# Item.net
KiCad netlist of a schematic drawn in Altium Designer
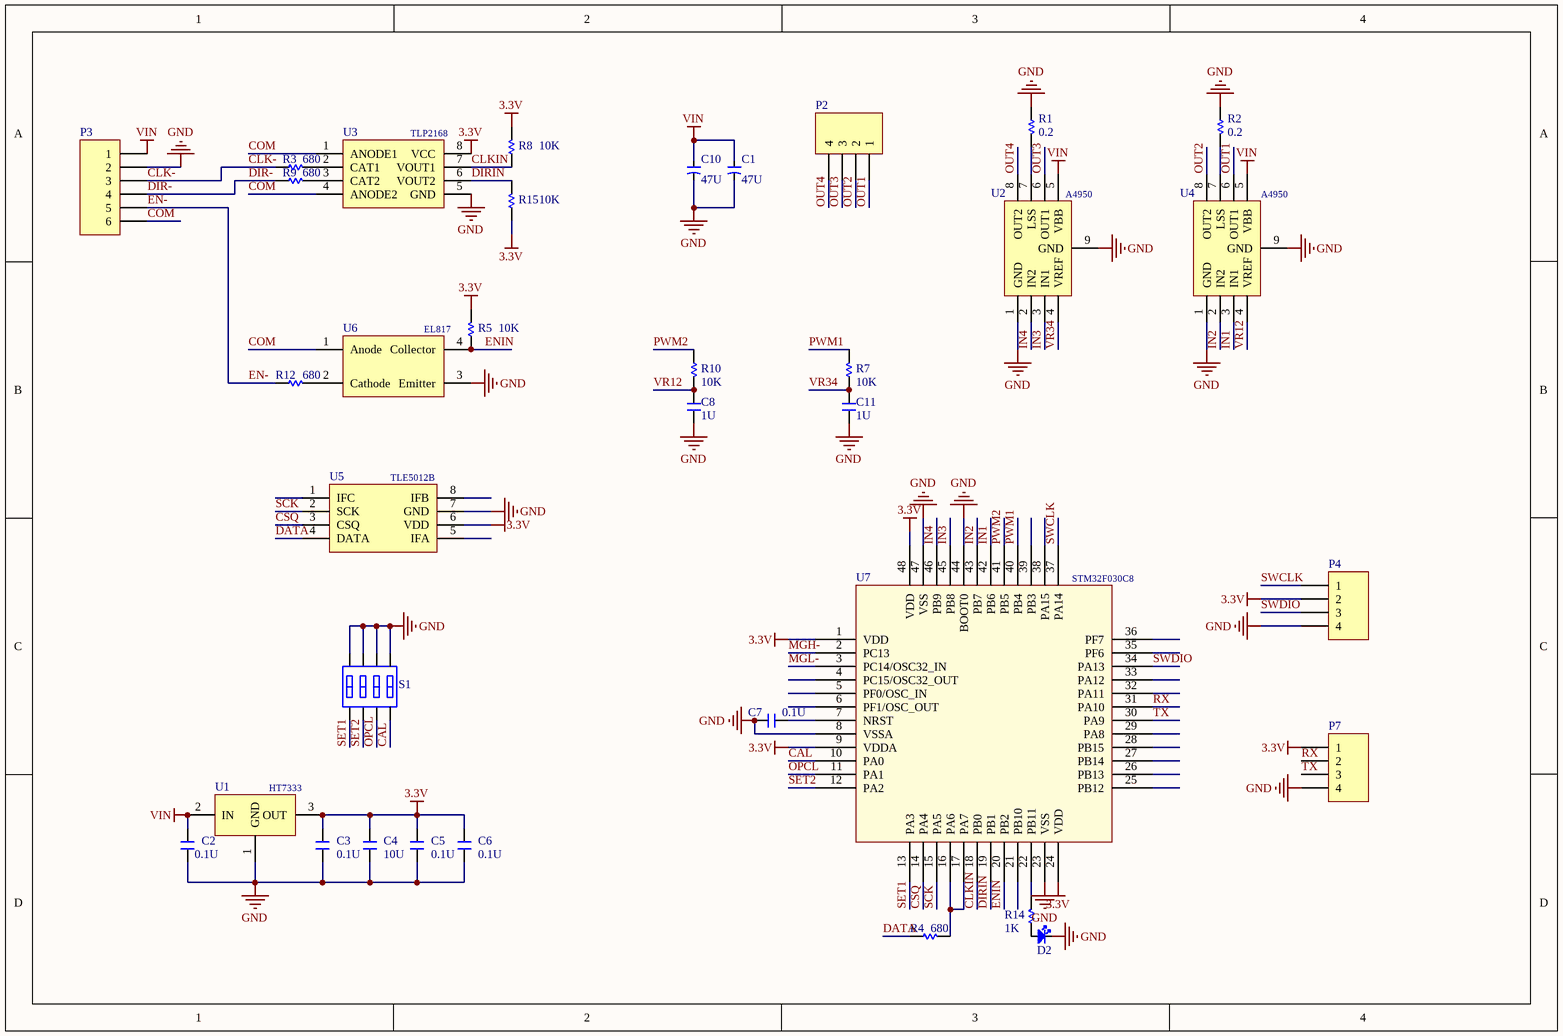
[diagram p0: Item.SchDoc]

(export (version "E")
  (design (tool "Eeschema 10.0.6"))
  (components
    (comp (ref "C1")
      (value "47U")
      (footprint "CAP6377")
      (description "Polarized Capacitor (Axial)")
      (fields (field (name "Comment") "CAP POL") (field (name "PUBLISHER") "Altium Limited"))
      (libsource (lib "MySchib") (part "CAP POL"))
    )
    (comp (ref "C2")
      (value "0.1U")
      (footprint "0805")
      (description "Capacitor")
      (fields (field (name "Comment") "CAP") (field (name "PUBLISHER") "Altium Limited"))
      (libsource (lib "MySchib") (part "CAP"))
    )
    (comp (ref "C3")
      (value "0.1U")
      (footprint "0805")
      (description "Capacitor")
      (fields (field (name "Comment") "CAP") (field (name "PUBLISHER") "Altium Limited"))
      (libsource (lib "MySchib") (part "CAP"))
    )
    (comp (ref "C4")
      (value "10U")
      (footprint "0805")
      (description "Capacitor")
      (fields (field (name "Comment") "CAP") (field (name "PUBLISHER") "Altium Limited"))
      (libsource (lib "MySchib") (part "CAP"))
    )
    (comp (ref "C5")
      (value "0.1U")
      (footprint "0805")
      (description "Capacitor")
      (fields (field (name "Comment") "CAP") (field (name "PUBLISHER") "Altium Limited"))
      (libsource (lib "MySchib") (part "CAP"))
    )
    (comp (ref "C6")
      (value "0.1U")
      (footprint "0805")
      (description "Capacitor")
      (fields (field (name "Comment") "CAP") (field (name "PUBLISHER") "Altium Limited"))
      (libsource (lib "MySchib") (part "CAP"))
    )
    (comp (ref "C7")
      (value "0.1U")
      (footprint "0805")
      (description "Capacitor")
      (fields (field (name "Comment") "CAP") (field (name "PUBLISHER") "Altium Limited"))
      (libsource (lib "MySchib") (part "CAP"))
    )
    (comp (ref "C8")
      (value "1U")
      (footprint "0805")
      (description "Capacitor")
      (fields (field (name "Comment") "CAP") (field (name "PUBLISHER") "Altium Limited"))
      (libsource (lib "MySchib") (part "CAP"))
    )
    (comp (ref "C10")
      (value "47U")
      (footprint "CAP6377")
      (description "Polarized Capacitor (Axial)")
      (fields (field (name "Comment") "CAP POL") (field (name "PUBLISHER") "Altium Limited"))
      (libsource (lib "MySchib") (part "CAP POL"))
    )
    (comp (ref "C11")
      (value "1U")
      (footprint "0805")
      (description "Capacitor")
      (fields (field (name "Comment") "CAP") (field (name "PUBLISHER") "Altium Limited"))
      (libsource (lib "MySchib") (part "CAP"))
    )
    (comp (ref "D2")
      (value "LED")
      (footprint "0805")
      (description "Typical INFRARED GaAs LED")
      (fields (field (name "PUBLISHER") "Altium Limited"))
      (libsource (lib "MySchib") (part "LED"))
    )
    (comp (ref "P2")
      (value "HEADER4")
      (footprint "XH-4")
      (description "Header, 4-Pin")
      (fields (field (name "PUBLISHER") "Altium Limited"))
      (libsource (lib "MySchib") (part "HEADER4"))
    )
    (comp (ref "P3")
      (value "HEADER6")
      (footprint "XH-6")
      (description "Header, 6-Pin")
      (fields (field (name "PUBLISHER") "Altium Limited"))
      (libsource (lib "MySchib") (part "HEADER6"))
    )
    (comp (ref "P4")
      (value "HEADER4")
      (footprint "4P-1.27MM")
      (description "Header, 4-Pin")
      (fields (field (name "PUBLISHER") "Altium Limited"))
      (libsource (lib "MySchib") (part "HEADER4"))
    )
    (comp (ref "P7")
      (value "HEADER4")
      (footprint "4P-1.27MM")
      (description "Header, 4-Pin")
      (fields (field (name "PUBLISHER") "Altium Limited"))
      (libsource (lib "MySchib") (part "HEADER4"))
    )
    (comp (ref "R1")
      (value "0.2")
      (footprint "1206")
      (description "Resistor")
      (fields (field (name "Comment") "RES") (field (name "PUBLISHER") "Altium Limited"))
      (libsource (lib "MySchib") (part "RES"))
    )
    (comp (ref "R2")
      (value "0.2")
      (footprint "1206")
      (description "Resistor")
      (fields (field (name "Comment") "RES") (field (name "PUBLISHER") "Altium Limited"))
      (libsource (lib "MySchib") (part "RES"))
    )
    (comp (ref "R3")
      (value "680")
      (footprint "0805")
      (description "Resistor")
      (fields (field (name "Comment") "RES") (field (name "PUBLISHER") "Altium Limited"))
      (libsource (lib "MySchib") (part "RES"))
    )
    (comp (ref "R4")
      (value "680")
      (footprint "0805")
      (description "Resistor")
      (fields (field (name "Comment") "RES") (field (name "PUBLISHER") "Altium Limited"))
      (libsource (lib "MySchib") (part "RES"))
    )
    (comp (ref "R5")
      (value "10K")
      (footprint "0805")
      (description "Resistor")
      (fields (field (name "Comment") "RES") (field (name "PUBLISHER") "Altium Limited"))
      (libsource (lib "MySchib") (part "RES"))
    )
    (comp (ref "R7")
      (value "10K")
      (footprint "0805")
      (description "Resistor")
      (fields (field (name "Comment") "RES") (field (name "PUBLISHER") "Altium Limited"))
      (libsource (lib "MySchib") (part "RES"))
    )
    (comp (ref "R8")
      (value "10K")
      (footprint "0805")
      (description "Resistor")
      (fields (field (name "Comment") "RES") (field (name "PUBLISHER") "Altium Limited"))
      (libsource (lib "MySchib") (part "RES"))
    )
    (comp (ref "R9")
      (value "680")
      (footprint "0805")
      (description "Resistor")
      (fields (field (name "Comment") "RES") (field (name "PUBLISHER") "Altium Limited"))
      (libsource (lib "MySchib") (part "RES"))
    )
    (comp (ref "R10")
      (value "10K")
      (footprint "0805")
      (description "Resistor")
      (fields (field (name "Comment") "RES") (field (name "PUBLISHER") "Altium Limited"))
      (libsource (lib "MySchib") (part "RES"))
    )
    (comp (ref "R12")
      (value "680")
      (footprint "0805")
      (description "Resistor")
      (fields (field (name "Comment") "RES") (field (name "PUBLISHER") "Altium Limited"))
      (libsource (lib "MySchib") (part "RES"))
    )
    (comp (ref "R14")
      (value "1K")
      (footprint "0805")
      (description "Resistor")
      (fields (field (name "Comment") "RES") (field (name "PUBLISHER") "Altium Limited"))
      (libsource (lib "MySchib") (part "RES"))
    )
    (comp (ref "R15")
      (value "10K")
      (footprint "0805")
      (description "Resistor")
      (fields (field (name "Comment") "RES") (field (name "PUBLISHER") "Altium Limited"))
      (libsource (lib "MySchib") (part "RES"))
    )
    (comp (ref "S1")
      (value "SWDIP-4")
      (footprint "SWDIP-4")
      (description "DIP Switch, 4Position, SPST")
      (fields (field (name "PUBLISHER") "Altium Limited"))
      (libsource (lib "MySchib") (part "SWDIP-4"))
    )
    (comp (ref "U1")
      (value "HT7333")
      (footprint "SOT89")
      (description "Positive Voltage Regulator")
      (fields (field (name "PUBLISHER") "Altium Limited"))
      (libsource (lib "MySchib") (part "HT7333"))
    )
    (comp (ref "U2")
      (value "A4950")
      (footprint "SOIC-8_A4950")
      (description "Dual Full-Bridge  DMOS PWM Motor Driver")
      (libsource (lib "MySchib") (part "A4950"))
    )
    (comp (ref "U3")
      (value "TLP2168")
      (footprint "SO-8_3.9mm")
      (description "HIGH SPEED 10MBit/s LOGIC GATE  PHOTOCOUPLER")
      (libsource (lib "MySchib") (part "TLP2168"))
    )
    (comp (ref "U4")
      (value "A4950")
      (footprint "SOIC-8_A4950")
      (description "Dual Full-Bridge  DMOS PWM Motor Driver")
      (libsource (lib "MySchib") (part "A4950"))
    )
    (comp (ref "U5")
      (value "TLE5012B")
      (footprint "PG-DSO-8F")
      (description "GMR-Based Angle Sensor")
      (libsource (lib "MySchib") (part "TLE5012B"))
    )
    (comp (ref "U6")
      (value "EL817")
      (footprint "SOP-4_P2.54")
      (description "4 PIN PHOTOTRANSISTOR")
      (libsource (lib "MySchib") (part "EL817"))
    )
    (comp (ref "U7")
      (value "STM32F030C8")
      (footprint "LQFP-48_7x7x05P")
      (description "ST Microcontroller")
      (libsource (lib "MySchib") (part "STM32F030C8"))
    )
  )
  (nets
    (net (code "1") (name "/CAL") (class "Default")
      (node (ref "S1") (pin "7") (pinfunction "A4_7") (pintype "passive"))
      (node (ref "U7") (pin "10") (pinfunction "PA0_10") (pintype "passive"))
    )
    (net (code "2") (name "/CLK-") (class "Default")
      (node (ref "P3") (pin "3") (pinfunction "3_3") (pintype "passive"))
      (node (ref "R3") (pin "1") (pinfunction "1_1") (pintype "passive"))
    )
    (net (code "3") (name "/CLKIN") (class "Default")
      (node (ref "R8") (pin "1") (pinfunction "1_1") (pintype "passive"))
      (node (ref "U3") (pin "7") (pinfunction "VOUT1_7") (pintype "passive"))
      (node (ref "U7") (pin "18") (pinfunction "PB0_18") (pintype "passive"))
    )
    (net (code "4") (name "/COM") (class "Default")
      (node (ref "P3") (pin "6") (pinfunction "6_6") (pintype "passive"))
      (node (ref "U3") (pin "1") (pinfunction "ANODE1_1") (pintype "passive"))
      (node (ref "U3") (pin "4") (pinfunction "ANODE2_4") (pintype "passive"))
      (node (ref "U6") (pin "1") (pinfunction "Anode_1") (pintype "passive"))
    )
    (net (code "5") (name "/CSQ") (class "Default")
      (node (ref "U5") (pin "3") (pinfunction "CSQ_3") (pintype "passive"))
      (node (ref "U7") (pin "14") (pinfunction "PA4_14") (pintype "passive"))
    )
    (net (code "6") (name "/DATA") (class "Default")
      (node (ref "R4") (pin "1") (pinfunction "1_1") (pintype "passive"))
      (node (ref "U5") (pin "4") (pinfunction "DATA_4") (pintype "passive"))
    )
    (net (code "7") (name "/DIR-") (class "Default")
      (node (ref "P3") (pin "4") (pinfunction "4_4") (pintype "passive"))
      (node (ref "R9") (pin "1") (pinfunction "1_1") (pintype "passive"))
    )
    (net (code "8") (name "/DIRIN") (class "Default")
      (node (ref "R15") (pin "2") (pinfunction "2_2") (pintype "passive"))
      (node (ref "U3") (pin "6") (pinfunction "VOUT2_6") (pintype "passive"))
      (node (ref "U7") (pin "19") (pinfunction "PB1_19") (pintype "passive"))
    )
    (net (code "9") (name "/EN-") (class "Default")
      (node (ref "P3") (pin "5") (pinfunction "5_5") (pintype "passive"))
      (node (ref "R12") (pin "1") (pinfunction "1_1") (pintype "passive"))
    )
    (net (code "10") (name "/ENIN") (class "Default")
      (node (ref "R5") (pin "1") (pinfunction "1_1") (pintype "passive"))
      (node (ref "U6") (pin "4") (pinfunction "Collector_4") (pintype "passive"))
      (node (ref "U7") (pin "20") (pinfunction "PB2_20") (pintype "passive"))
    )
    (net (code "11") (name "/IN1") (class "Default")
      (node (ref "U4") (pin "3") (pinfunction "IN1_3") (pintype "passive"))
      (node (ref "U7") (pin "42") (pinfunction "PB6_42") (pintype "passive"))
    )
    (net (code "12") (name "/IN2") (class "Default")
      (node (ref "U4") (pin "2") (pinfunction "IN2_2") (pintype "passive"))
      (node (ref "U7") (pin "43") (pinfunction "PB7_43") (pintype "passive"))
    )
    (net (code "13") (name "/IN3") (class "Default")
      (node (ref "U2") (pin "3") (pinfunction "IN1_3") (pintype "passive"))
      (node (ref "U7") (pin "45") (pinfunction "PB8_45") (pintype "passive"))
    )
    (net (code "14") (name "/IN4") (class "Default")
      (node (ref "U2") (pin "2") (pinfunction "IN2_2") (pintype "passive"))
      (node (ref "U7") (pin "46") (pinfunction "PB9_46") (pintype "passive"))
    )
    (net (code "15") (name "/MGH-") (class "Default")
      (node (ref "U7") (pin "2") (pinfunction "PC13_2") (pintype "passive"))
    )
    (net (code "16") (name "/MGL-") (class "Default")
      (node (ref "U7") (pin "3") (pinfunction "PC14/OSC32_IN_3") (pintype "passive"))
    )
    (net (code "17") (name "/OPCL") (class "Default")
      (node (ref "S1") (pin "5") (pinfunction "A3_5") (pintype "passive"))
      (node (ref "U7") (pin "11") (pinfunction "PA1_11") (pintype "passive"))
    )
    (net (code "18") (name "/OUT1") (class "Default")
      (node (ref "P2") (pin "1") (pinfunction "1_1") (pintype "passive"))
      (node (ref "U4") (pin "6") (pinfunction "OUT1_6") (pintype "passive"))
    )
    (net (code "19") (name "/OUT2") (class "Default")
      (node (ref "P2") (pin "2") (pinfunction "2_2") (pintype "passive"))
      (node (ref "U4") (pin "8") (pinfunction "OUT2_8") (pintype "passive"))
    )
    (net (code "20") (name "/OUT3") (class "Default")
      (node (ref "P2") (pin "3") (pinfunction "3_3") (pintype "passive"))
      (node (ref "U2") (pin "6") (pinfunction "OUT1_6") (pintype "passive"))
    )
    (net (code "21") (name "/OUT4") (class "Default")
      (node (ref "P2") (pin "4") (pinfunction "4_4") (pintype "passive"))
      (node (ref "U2") (pin "8") (pinfunction "OUT2_8") (pintype "passive"))
    )
    (net (code "22") (name "/PWM1") (class "Default")
      (node (ref "R7") (pin "2") (pinfunction "2_2") (pintype "passive"))
      (node (ref "U7") (pin "40") (pinfunction "PB4_40") (pintype "passive"))
    )
    (net (code "23") (name "/PWM2") (class "Default")
      (node (ref "R10") (pin "1") (pinfunction "1_1") (pintype "passive"))
      (node (ref "U7") (pin "41") (pinfunction "PB5_41") (pintype "passive"))
    )
    (net (code "24") (name "/RX") (class "Default")
      (node (ref "P7") (pin "2") (pinfunction "2_2") (pintype "passive"))
      (node (ref "U7") (pin "31") (pinfunction "PA10_31") (pintype "passive"))
    )
    (net (code "25") (name "/SCK") (class "Default")
      (node (ref "U5") (pin "2") (pinfunction "SCK_2") (pintype "passive"))
      (node (ref "U7") (pin "15") (pinfunction "PA5_15") (pintype "passive"))
    )
    (net (code "26") (name "/SET1") (class "Default")
      (node (ref "S1") (pin "1") (pinfunction "A1_1") (pintype "passive"))
      (node (ref "U7") (pin "13") (pinfunction "PA3_13") (pintype "passive"))
    )
    (net (code "27") (name "/SET2") (class "Default")
      (node (ref "S1") (pin "3") (pinfunction "A2_3") (pintype "passive"))
      (node (ref "U7") (pin "12") (pinfunction "PA2_12") (pintype "passive"))
    )
    (net (code "28") (name "/SWCLK") (class "Default")
      (node (ref "P4") (pin "1") (pinfunction "1_1") (pintype "passive"))
      (node (ref "U7") (pin "37") (pinfunction "PA14_37") (pintype "passive"))
    )
    (net (code "29") (name "/SWDIO") (class "Default")
      (node (ref "P4") (pin "3") (pinfunction "3_3") (pintype "passive"))
      (node (ref "U7") (pin "34") (pinfunction "PA13_34") (pintype "passive"))
    )
    (net (code "30") (name "/TX") (class "Default")
      (node (ref "P7") (pin "3") (pinfunction "3_3") (pintype "passive"))
      (node (ref "U7") (pin "30") (pinfunction "PA9_30") (pintype "passive"))
    )
    (net (code "31") (name "/VR12") (class "Default")
      (node (ref "C8") (pin "1") (pinfunction "1_1") (pintype "passive"))
      (node (ref "R10") (pin "2") (pinfunction "2_2") (pintype "passive"))
      (node (ref "U4") (pin "4") (pinfunction "VREF_4") (pintype "passive"))
    )
    (net (code "32") (name "/VR34") (class "Default")
      (node (ref "C11") (pin "1") (pinfunction "1_1") (pintype "passive"))
      (node (ref "R7") (pin "1") (pinfunction "1_1") (pintype "passive"))
      (node (ref "U2") (pin "4") (pinfunction "VREF_4") (pintype "passive"))
    )
    (net (code "33") (name "3.3V") (class "Default")
      (node (ref "C3") (pin "1") (pinfunction "1_1") (pintype "passive"))
      (node (ref "C4") (pin "1") (pinfunction "1_1") (pintype "passive"))
      (node (ref "C5") (pin "1") (pinfunction "1_1") (pintype "passive"))
      (node (ref "C6") (pin "1") (pinfunction "1_1") (pintype "passive"))
      (node (ref "P4") (pin "2") (pinfunction "2_2") (pintype "passive"))
      (node (ref "P7") (pin "1") (pinfunction "1_1") (pintype "passive"))
      (node (ref "R15") (pin "1") (pinfunction "1_1") (pintype "passive"))
      (node (ref "R5") (pin "2") (pinfunction "2_2") (pintype "passive"))
      (node (ref "R8") (pin "2") (pinfunction "2_2") (pintype "passive"))
      (node (ref "U1") (pin "3") (pinfunction "OUT_3") (pintype "power_in"))
      (node (ref "U3") (pin "8") (pinfunction "VCC_8") (pintype "passive"))
      (node (ref "U5") (pin "6") (pinfunction "VDD_6") (pintype "passive"))
      (node (ref "U7") (pin "1") (pinfunction "VDD_1") (pintype "passive"))
      (node (ref "U7") (pin "24") (pinfunction "VDD_24") (pintype "passive"))
      (node (ref "U7") (pin "48") (pinfunction "VDD_48") (pintype "passive"))
      (node (ref "U7") (pin "9") (pinfunction "VDDA_9") (pintype "passive"))
    )
    (net (code "34") (name "GND") (class "Default")
      (node (ref "C1") (pin "2") (pinfunction "2_2") (pintype "passive"))
      (node (ref "C10") (pin "2") (pinfunction "2_2") (pintype "passive"))
      (node (ref "C11") (pin "2") (pinfunction "2_2") (pintype "passive"))
      (node (ref "C2") (pin "2") (pinfunction "2_2") (pintype "passive"))
      (node (ref "C3") (pin "2") (pinfunction "2_2") (pintype "passive"))
      (node (ref "C4") (pin "2") (pinfunction "2_2") (pintype "passive"))
      (node (ref "C5") (pin "2") (pinfunction "2_2") (pintype "passive"))
      (node (ref "C6") (pin "2") (pinfunction "2_2") (pintype "passive"))
      (node (ref "C7") (pin "1") (pinfunction "1_1") (pintype "passive"))
      (node (ref "C8") (pin "2") (pinfunction "2_2") (pintype "passive"))
      (node (ref "D2") (pin "2") (pinfunction "K_2") (pintype "passive"))
      (node (ref "P3") (pin "2") (pinfunction "2_2") (pintype "passive"))
      (node (ref "P4") (pin "4") (pinfunction "4_4") (pintype "passive"))
      (node (ref "P7") (pin "4") (pinfunction "4_4") (pintype "passive"))
      (node (ref "R1") (pin "1") (pinfunction "1_1") (pintype "passive"))
      (node (ref "R2") (pin "1") (pinfunction "1_1") (pintype "passive"))
      (node (ref "S1") (pin "2") (pinfunction "B1_2") (pintype "passive"))
      (node (ref "S1") (pin "4") (pinfunction "B2_4") (pintype "passive"))
      (node (ref "S1") (pin "6") (pinfunction "B3_6") (pintype "passive"))
      (node (ref "S1") (pin "8") (pinfunction "B4_8") (pintype "passive"))
      (node (ref "U1") (pin "1") (pinfunction "GND_1") (pintype "power_in"))
      (node (ref "U2") (pin "1") (pinfunction "GND_1") (pintype "passive"))
      (node (ref "U2") (pin "9") (pinfunction "GND_9") (pintype "passive"))
      (node (ref "U3") (pin "5") (pinfunction "GND_5") (pintype "passive"))
      (node (ref "U4") (pin "1") (pinfunction "GND_1") (pintype "passive"))
      (node (ref "U4") (pin "9") (pinfunction "GND_9") (pintype "passive"))
      (node (ref "U5") (pin "7") (pinfunction "GND_7") (pintype "passive"))
      (node (ref "U6") (pin "3") (pinfunction "Emitter_3") (pintype "passive"))
      (node (ref "U7") (pin "23") (pinfunction "VSS_23") (pintype "passive"))
      (node (ref "U7") (pin "44") (pinfunction "BOOT0_44") (pintype "passive"))
      (node (ref "U7") (pin "47") (pinfunction "VSS_47") (pintype "passive"))
      (node (ref "U7") (pin "8") (pinfunction "VSSA_8") (pintype "passive"))
    )
    (net (code "35") (name "Net-(D2-A)") (class "Default")
      (node (ref "D2") (pin "1") (pinfunction "A_1") (pintype "passive"))
      (node (ref "R14") (pin "1") (pinfunction "1_1") (pintype "passive"))
    )
    (net (code "36") (name "Net-(U2-LSS)") (class "Default")
      (node (ref "R1") (pin "2") (pinfunction "2_2") (pintype "passive"))
      (node (ref "U2") (pin "7") (pinfunction "LSS_7") (pintype "passive"))
    )
    (net (code "37") (name "Net-(U3-CAT1)") (class "Default")
      (node (ref "R3") (pin "2") (pinfunction "2_2") (pintype "passive"))
      (node (ref "U3") (pin "2") (pinfunction "CAT1_2") (pintype "passive"))
    )
    (net (code "38") (name "Net-(U3-CAT2)") (class "Default")
      (node (ref "R9") (pin "2") (pinfunction "2_2") (pintype "passive"))
      (node (ref "U3") (pin "3") (pinfunction "CAT2_3") (pintype "passive"))
    )
    (net (code "39") (name "Net-(U4-LSS)") (class "Default")
      (node (ref "R2") (pin "2") (pinfunction "2_2") (pintype "passive"))
      (node (ref "U4") (pin "7") (pinfunction "LSS_7") (pintype "passive"))
    )
    (net (code "40") (name "Net-(U6-Cathode)") (class "Default")
      (node (ref "R12") (pin "2") (pinfunction "2_2") (pintype "passive"))
      (node (ref "U6") (pin "2") (pinfunction "Cathode_2") (pintype "passive"))
    )
    (net (code "41") (name "Net-(U7-NRST)") (class "Default")
      (node (ref "C7") (pin "2") (pinfunction "2_2") (pintype "passive"))
      (node (ref "U7") (pin "7") (pinfunction "NRST_7") (pintype "passive"))
    )
    (net (code "42") (name "Net-(U7-PA6)") (class "Default")
      (node (ref "R4") (pin "2") (pinfunction "2_2") (pintype "passive"))
      (node (ref "U7") (pin "16") (pinfunction "PA6_16") (pintype "passive"))
      (node (ref "U7") (pin "17") (pinfunction "PA7_17") (pintype "passive"))
    )
    (net (code "43") (name "Net-(U7-PB11)") (class "Default")
      (node (ref "R14") (pin "2") (pinfunction "2_2") (pintype "passive"))
      (node (ref "U7") (pin "22") (pinfunction "PB11_22") (pintype "passive"))
    )
    (net (code "44") (name "VIN") (class "Default")
      (node (ref "C1") (pin "1") (pinfunction "1_1") (pintype "passive"))
      (node (ref "C10") (pin "1") (pinfunction "1_1") (pintype "passive"))
      (node (ref "C2") (pin "1") (pinfunction "1_1") (pintype "passive"))
      (node (ref "P3") (pin "1") (pinfunction "1_1") (pintype "passive"))
      (node (ref "U1") (pin "2") (pinfunction "IN_2") (pintype "power_in"))
      (node (ref "U2") (pin "5") (pinfunction "VBB_5") (pintype "passive"))
      (node (ref "U4") (pin "5") (pinfunction "VBB_5") (pintype "passive"))
    )
    (net (code "45") (name "unconnected-(U5-IFA-Pad5)") (class "Default")
      (node (ref "U5") (pin "5") (pinfunction "IFA_5") (pintype "passive"))
    )
    (net (code "46") (name "unconnected-(U5-IFB-Pad8)") (class "Default")
      (node (ref "U5") (pin "8") (pinfunction "IFB_8") (pintype "passive"))
    )
    (net (code "47") (name "unconnected-(U5-IFC-Pad1)") (class "Default")
      (node (ref "U5") (pin "1") (pinfunction "IFC_1") (pintype "passive"))
    )
    (net (code "48") (name "unconnected-(U7-PA8-Pad29)") (class "Default")
      (node (ref "U7") (pin "29") (pinfunction "PA8_29") (pintype "passive"))
    )
    (net (code "49") (name "unconnected-(U7-PA11-Pad32)") (class "Default")
      (node (ref "U7") (pin "32") (pinfunction "PA11_32") (pintype "passive"))
    )
    (net (code "50") (name "unconnected-(U7-PA12-Pad33)") (class "Default")
      (node (ref "U7") (pin "33") (pinfunction "PA12_33") (pintype "passive"))
    )
    (net (code "51") (name "unconnected-(U7-PA15-Pad38)") (class "Default")
      (node (ref "U7") (pin "38") (pinfunction "PA15_38") (pintype "passive"))
    )
    (net (code "52") (name "unconnected-(U7-PB3-Pad39)") (class "Default")
      (node (ref "U7") (pin "39") (pinfunction "PB3_39") (pintype "passive"))
    )
    (net (code "53") (name "unconnected-(U7-PB10-Pad21)") (class "Default")
      (node (ref "U7") (pin "21") (pinfunction "PB10_21") (pintype "passive"))
    )
    (net (code "54") (name "unconnected-(U7-PB12-Pad25)") (class "Default")
      (node (ref "U7") (pin "25") (pinfunction "PB12_25") (pintype "passive"))
    )
    (net (code "55") (name "unconnected-(U7-PB13-Pad26)") (class "Default")
      (node (ref "U7") (pin "26") (pinfunction "PB13_26") (pintype "passive"))
    )
    (net (code "56") (name "unconnected-(U7-PB14-Pad27)") (class "Default")
      (node (ref "U7") (pin "27") (pinfunction "PB14_27") (pintype "passive"))
    )
    (net (code "57") (name "unconnected-(U7-PB15-Pad28)") (class "Default")
      (node (ref "U7") (pin "28") (pinfunction "PB15_28") (pintype "passive"))
    )
    (net (code "58") (name "unconnected-(U7-PC15{slash}OSC32_OUT-Pad4)") (class "Default")
      (node (ref "U7") (pin "4") (pinfunction "PC15/OSC32_OUT_4") (pintype "power_in"))
    )
    (net (code "59") (name "unconnected-(U7-PF0{slash}OSC_IN-Pad5)") (class "Default")
      (node (ref "U7") (pin "5") (pinfunction "PF0/OSC_IN_5") (pintype "power_in"))
    )
    (net (code "60") (name "unconnected-(U7-PF1{slash}OSC_OUT-Pad6)") (class "Default")
      (node (ref "U7") (pin "6") (pinfunction "PF1/OSC_OUT_6") (pintype "power_in"))
    )
    (net (code "61") (name "unconnected-(U7-PF6-Pad35)") (class "Default")
      (node (ref "U7") (pin "35") (pinfunction "PF6_35") (pintype "passive"))
    )
    (net (code "62") (name "unconnected-(U7-PF7-Pad36)") (class "Default")
      (node (ref "U7") (pin "36") (pinfunction "PF7_36") (pintype "passive"))
    )
  )
)
